# SAMD21.net
KiCad netlist of a schematic drawn in Altium Designer
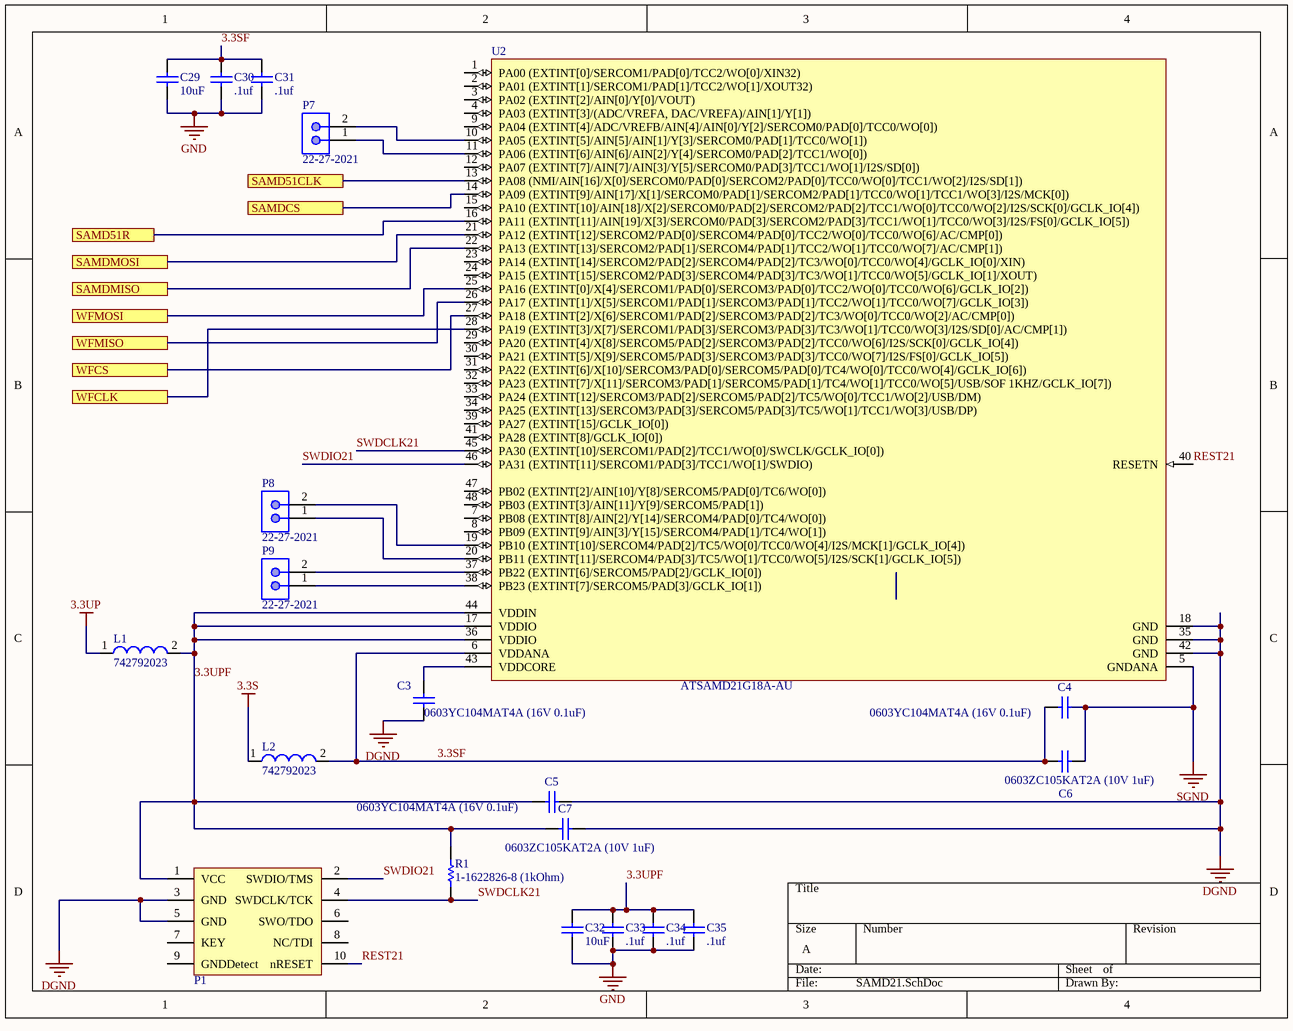
[diagram p0: SAMD21.SchDoc]

(export (version "E")
  (design (tool "Eeschema 10.0.6"))
  (components
    (comp (ref "C3")
      (value "0603YC104MAT4A (16V 0.1uF)")
      (footprint "CAPC1608X90X35LL15T15")
      (fields
        (field (name "PART NUMBER") "0603YC104MAT4A")
        (field (name "MANUFACTURER") "AVX Interconnect / Elco")
      )
      (libsource (lib "Altium Content Vault") (part "CAP"))
    )
    (comp (ref "C4")
      (value "0603YC104MAT4A (16V 0.1uF)")
      (footprint "CAPC1608X90X35LL15T15")
      (fields
        (field (name "PART NUMBER") "0603YC104MAT4A")
        (field (name "MANUFACTURER") "AVX Interconnect / Elco")
      )
      (libsource (lib "Altium Content Vault") (part "CAP"))
    )
    (comp (ref "C5")
      (value "0603YC104MAT4A (16V 0.1uF)")
      (footprint "CAPC1608X90X35LL15T15")
      (fields
        (field (name "PART NUMBER") "0603YC104MAT4A")
        (field (name "MANUFACTURER") "AVX Interconnect / Elco")
      )
      (libsource (lib "Altium Content Vault") (part "CAP"))
    )
    (comp (ref "C6")
      (value "0603ZC105KAT2A (10V 1uF)")
      (footprint "CAPC1608X90X35LL15T15")
      (fields
        (field (name "PART NUMBER") "0603ZC105KAT2A")
        (field (name "MANUFACTURER") "AVX Interconnect / Elco")
      )
      (libsource (lib "Altium Content Vault") (part "CAP"))
    )
    (comp (ref "C7")
      (value "0603ZC105KAT2A (10V 1uF)")
      (footprint "CAPC1608X90X35LL15T15")
      (fields
        (field (name "PART NUMBER") "0603ZC105KAT2A")
        (field (name "MANUFACTURER") "AVX Interconnect / Elco")
      )
      (libsource (lib "Altium Content Vault") (part "CAP"))
    )
    (comp (ref "C29")
      (value "10uF")
      (footprint "CAPC1608X90X35NL10T15")
      (fields (field (name "PART NUMBER") "GRM188R60J106ME47D") (field (name "MANUFACTURER") "Murata"))
      (libsource (lib "Altium Content Vault") (part "CAP"))
    )
    (comp (ref "C30")
      (value ".1uf")
      (footprint "CAPC2013X94X50NL20T25")
      (fields
        (field (name "PART NUMBER") "0805YC104KAT2A")
        (field (name "MANUFACTURER") "AVX Interconnect / Elco")
      )
      (libsource (lib "Altium Content Vault") (part "CAP"))
    )
    (comp (ref "C31")
      (value ".1uf")
      (footprint "CAPC2013X94X50NL20T25")
      (fields
        (field (name "PART NUMBER") "0805YC104KAT2A")
        (field (name "MANUFACTURER") "AVX Interconnect / Elco")
      )
      (libsource (lib "Altium Content Vault") (part "CAP"))
    )
    (comp (ref "C32")
      (value "10uF")
      (footprint "CAPC1608X90X35NL10T15")
      (fields (field (name "PART NUMBER") "GRM188R60J106ME47D") (field (name "MANUFACTURER") "Murata"))
      (libsource (lib "Altium Content Vault") (part "CAP"))
    )
    (comp (ref "C33")
      (value ".1uf")
      (footprint "CAPC2013X94X50NL20T25")
      (fields
        (field (name "PART NUMBER") "0805YC104KAT2A")
        (field (name "MANUFACTURER") "AVX Interconnect / Elco")
      )
      (libsource (lib "Altium Content Vault") (part "CAP"))
    )
    (comp (ref "C34")
      (value ".1uf")
      (footprint "CAPC2013X94X50NL20T25")
      (fields
        (field (name "PART NUMBER") "0805YC104KAT2A")
        (field (name "MANUFACTURER") "AVX Interconnect / Elco")
      )
      (libsource (lib "Altium Content Vault") (part "CAP"))
    )
    (comp (ref "C35")
      (value ".1uf")
      (footprint "CAPC2013X94X50NL20T25")
      (fields
        (field (name "PART NUMBER") "0805YC104KAT2A")
        (field (name "MANUFACTURER") "AVX Interconnect / Elco")
      )
      (libsource (lib "Altium Content Vault") (part "CAP"))
    )
    (comp (ref "L1")
      (value "742792023")
      (footprint "SMD-0805")
      (description "SMD EMI Suppression Ferrite Bead WE-CBF, Z = 120 Ohm")
      (libsource (lib "Altium Content Vault") (part "PAS-IND-INDUCTOR-2"))
    )
    (comp (ref "L2")
      (value "742792023")
      (footprint "SMD-0805")
      (description "SMD EMI Suppression Ferrite Bead WE-CBF, Z = 120 Ohm")
      (libsource (lib "Altium Content Vault") (part "PAS-IND-INDUCTOR-2"))
    )
    (comp (ref "P1")
      (value "3220-10-0100-00 Pin connector for Cotex Programmers")
      (description "3220-10-0100-00 Pin connector from DigiKey")
      (libsource (lib "3220-10-0100-00") (part "3220-10-0100-00"))
    )
    (comp (ref "P7")
      (value "22-27-2021")
      (footprint "MOLX-22-27-2021_V")
      (fields (field (name "MANUFACTURER") "Molex") (field (name "PARTNUMBER") "0022272021"))
      (libsource (lib "Altium Content Vault") (part "CN-1P-M-R2"))
    )
    (comp (ref "P8")
      (value "22-27-2021")
      (footprint "MOLX-22-27-2021_V")
      (fields (field (name "MANUFACTURER") "Molex") (field (name "PARTNUMBER") "0022272021"))
      (libsource (lib "Altium Content Vault") (part "CN-1P-M-R2"))
    )
    (comp (ref "P9")
      (value "22-27-2021")
      (footprint "MOLX-22-27-2021_V")
      (fields (field (name "MANUFACTURER") "Molex") (field (name "PARTNUMBER") "0022272021"))
      (libsource (lib "Altium Content Vault") (part "CN-1P-M-R2"))
    )
    (comp (ref "R1")
      (value "1-1622826-8 (1kOhm)")
      (footprint "RESC1005X40X25ML10T10")
      (fields
        (field (name "MANUFACTURER") "TE Connectivity / AMP")
        (field (name "PART NUMBER") "1-1622826-8")
      )
      (libsource (lib "Altium Content Vault") (part "RES"))
    )
    (comp (ref "U2")
      (value "ATSAMD21G18A-AU")
      (footprint "ATML-TQFP48_M")
      (fields (field (name "MANUFACTURER") "Atmel"))
      (libsource (lib "Altium Content Vault") (part "ATML-ATSAMD21G18_17_16_15A-TQFP48"))
    )
  )
  (nets
    (net (code "1") (name "/3.3SF") (class "Default")
      (node (ref "C29") (pin "2") (pinfunction "2_2") (pintype "passive"))
      (node (ref "C30") (pin "2") (pinfunction "2_2") (pintype "passive"))
      (node (ref "C31") (pin "2") (pinfunction "2_2") (pintype "passive"))
      (node (ref "C4") (pin "2") (pinfunction "2_2") (pintype "passive"))
      (node (ref "C6") (pin "1") (pinfunction "1_1") (pintype "passive"))
      (node (ref "L2") (pin "2") (pinfunction "2_2") (pintype "passive"))
      (node (ref "U2") (pin "6") (pinfunction "VDDANA_6") (pintype "power_in"))
    )
    (net (code "2") (name "/3.3UPF") (class "Default")
      (node (ref "C32") (pin "2") (pinfunction "2_2") (pintype "passive"))
      (node (ref "C33") (pin "2") (pinfunction "2_2") (pintype "passive"))
      (node (ref "C34") (pin "2") (pinfunction "2_2") (pintype "passive"))
      (node (ref "C35") (pin "2") (pinfunction "2_2") (pintype "passive"))
      (node (ref "C5") (pin "2") (pinfunction "2_2") (pintype "passive"))
      (node (ref "C7") (pin "1") (pinfunction "1_1") (pintype "passive"))
      (node (ref "L1") (pin "2") (pinfunction "2_2") (pintype "passive"))
      (node (ref "P1") (pin "1") (pinfunction "VCC_1") (pintype "passive"))
      (node (ref "R1") (pin "2") (pinfunction "2_2") (pintype "passive"))
      (node (ref "U2") (pin "17") (pinfunction "VDDIO_17") (pintype "power_in"))
      (node (ref "U2") (pin "36") (pinfunction "VDDIO_36") (pintype "power_in"))
      (node (ref "U2") (pin "44") (pinfunction "VDDIN_44") (pintype "power_in"))
    )
    (net (code "3") (name "/REST21") (class "Default")
      (node (ref "P1") (pin "10") (pinfunction "nRESET_10") (pintype "passive"))
      (node (ref "U2") (pin "40") (pinfunction "RESETN_40") (pintype "input"))
    )
    (net (code "4") (name "/SAMD51CLK") (class "Default")
      (node (ref "U2") (pin "13") (pinfunction "PA08_(NMI/AIN[16]/X[0]/SERCOM0/PAD[0]/SERCOM2/PAD[0]/TCC0/WO[0]/TCC1/WO[2]/I2S/SD[1])_13") (pintype "bidirectional"))
    )
    (net (code "5") (name "/SAMD51R") (class "Default")
      (node (ref "U2") (pin "16") (pinfunction "PA11_(EXTINT[11]/AIN[19]/X[3]/SERCOM0/PAD[3]/SERCOM2/PAD[3]/TCC1/WO[1]/TCC0/WO[3]/I2S/FS[0]/GCLK_IO[5])_16") (pintype "bidirectional"))
    )
    (net (code "6") (name "/SAMDCS") (class "Default")
      (node (ref "U2") (pin "14") (pinfunction "PA09_(EXTINT[9]/AIN[17]/X[1]/SERCOM0/PAD[1]/SERCOM2/PAD[1]/TCC0/WO[1]/TCC1/WO[3]/I2S/MCK[0])_14") (pintype "bidirectional"))
    )
    (net (code "7") (name "/SAMDMISO") (class "Default")
      (node (ref "U2") (pin "22") (pinfunction "PA13_(EXTINT[13]/SERCOM2/PAD[1]/SERCOM4/PAD[1]/TCC2/WO[1]/TCC0/WO[7]/AC/CMP[1])_22") (pintype "bidirectional"))
    )
    (net (code "8") (name "/SAMDMOSI") (class "Default")
      (node (ref "U2") (pin "21") (pinfunction "PA12_(EXTINT[12]/SERCOM2/PAD[0]/SERCOM4/PAD[0]/TCC2/WO[0]/TCC0/WO[6]/AC/CMP[0])_21") (pintype "bidirectional"))
    )
    (net (code "9") (name "/SWDCLK21") (class "Default")
      (node (ref "P1") (pin "4") (pinfunction "SWDCLK/TCK_4") (pintype "passive"))
      (node (ref "R1") (pin "1") (pinfunction "1_1") (pintype "passive"))
      (node (ref "U2") (pin "45") (pinfunction "PA30_(EXTINT[10]/SERCOM1/PAD[2]/TCC1/WO[0]/SWCLK/GCLK_IO[0])_45") (pintype "bidirectional"))
    )
    (net (code "10") (name "/SWDIO21") (class "Default")
      (node (ref "P1") (pin "2") (pinfunction "SWDIO/TMS_2") (pintype "passive"))
      (node (ref "U2") (pin "46") (pinfunction "PA31_(EXTINT[11]/SERCOM1/PAD[3]/TCC1/WO[1]/SWDIO)_46") (pintype "bidirectional"))
    )
    (net (code "11") (name "/WFCLK") (class "Default")
      (node (ref "U2") (pin "28") (pinfunction "PA19_(EXTINT[3]/X[7]/SERCOM1/PAD[3]/SERCOM3/PAD[3]/TC3/WO[1]/TCC0/WO[3]/I2S/SD[0]/AC/CMP[1])_28") (pintype "bidirectional"))
    )
    (net (code "12") (name "/WFCS") (class "Default")
      (node (ref "U2") (pin "27") (pinfunction "PA18_(EXTINT[2]/X[6]/SERCOM1/PAD[2]/SERCOM3/PAD[2]/TC3/WO[0]/TCC0/WO[2]/AC/CMP[0])_27") (pintype "bidirectional"))
    )
    (net (code "13") (name "/WFMISO") (class "Default")
      (node (ref "U2") (pin "26") (pinfunction "PA17_(EXTINT[1]/X[5]/SERCOM1/PAD[1]/SERCOM3/PAD[1]/TCC2/WO[1]/TCC0/WO[7]/GCLK_IO[3])_26") (pintype "bidirectional"))
    )
    (net (code "14") (name "/WFMOSI") (class "Default")
      (node (ref "U2") (pin "25") (pinfunction "PA16_(EXTINT[0]/X[4]/SERCOM1/PAD[0]/SERCOM3/PAD[0]/TCC2/WO[0]/TCC0/WO[6]/GCLK_IO[2])_25") (pintype "bidirectional"))
    )
    (net (code "15") (name "3.3S") (class "Default")
      (node (ref "L2") (pin "1") (pinfunction "1_1") (pintype "passive"))
    )
    (net (code "16") (name "3.3UP") (class "Default")
      (node (ref "L1") (pin "1") (pinfunction "1_1") (pintype "passive"))
    )
    (net (code "17") (name "DGND") (class "Default")
      (node (ref "C3") (pin "2") (pinfunction "2_2") (pintype "passive"))
      (node (ref "C5") (pin "1") (pinfunction "1_1") (pintype "passive"))
      (node (ref "C7") (pin "2") (pinfunction "2_2") (pintype "passive"))
      (node (ref "P1") (pin "3") (pinfunction "GND_3") (pintype "passive"))
      (node (ref "P1") (pin "5") (pinfunction "GND_5") (pintype "passive"))
      (node (ref "U2") (pin "18") (pinfunction "GND_18") (pintype "power_in"))
      (node (ref "U2") (pin "35") (pinfunction "GND_35") (pintype "power_in"))
      (node (ref "U2") (pin "42") (pinfunction "GND_42") (pintype "power_in"))
    )
    (net (code "18") (name "GND") (class "Default")
      (node (ref "C29") (pin "1") (pinfunction "1_1") (pintype "passive"))
      (node (ref "C30") (pin "1") (pinfunction "1_1") (pintype "passive"))
      (node (ref "C31") (pin "1") (pinfunction "1_1") (pintype "passive"))
      (node (ref "C32") (pin "1") (pinfunction "1_1") (pintype "passive"))
      (node (ref "C33") (pin "1") (pinfunction "1_1") (pintype "passive"))
      (node (ref "C34") (pin "1") (pinfunction "1_1") (pintype "passive"))
      (node (ref "C35") (pin "1") (pinfunction "1_1") (pintype "passive"))
    )
    (net (code "19") (name "Net-(U2-PA05_(EXTINT[5]{slash}AIN[5]{slash}AIN[1]{slash}Y[3]{slash}SERCOM0{slash}PAD[1]{slash}TCC0{slash}WO[1]))") (class "Default")
      (node (ref "P7") (pin "2") (pinfunction "2_2") (pintype "passive"))
      (node (ref "U2") (pin "10") (pinfunction "PA05_(EXTINT[5]/AIN[5]/AIN[1]/Y[3]/SERCOM0/PAD[1]/TCC0/WO[1])_10") (pintype "bidirectional"))
    )
    (net (code "20") (name "Net-(U2-PA06_(EXTINT[6]{slash}AIN[6]{slash}AIN[2]{slash}Y[4]{slash}SERCOM0{slash}PAD[2]{slash}TCC1{slash}WO[0]))") (class "Default")
      (node (ref "P7") (pin "1") (pinfunction "1_1") (pintype "passive"))
      (node (ref "U2") (pin "11") (pinfunction "PA06_(EXTINT[6]/AIN[6]/AIN[2]/Y[4]/SERCOM0/PAD[2]/TCC1/WO[0])_11") (pintype "bidirectional"))
    )
    (net (code "21") (name "Net-(U2-PB10_(EXTINT[10]{slash}SERCOM4{slash}PAD[2]{slash}TC5{slash}WO[0]{slash}TCC0{slash}WO[4]{slash}I2S{slash}MCK[1]{slash}GCLK_IO[4]))") (class "Default")
      (node (ref "P8") (pin "2") (pinfunction "2_2") (pintype "passive"))
      (node (ref "U2") (pin "19") (pinfunction "PB10_(EXTINT[10]/SERCOM4/PAD[2]/TC5/WO[0]/TCC0/WO[4]/I2S/MCK[1]/GCLK_IO[4])_19") (pintype "bidirectional"))
    )
    (net (code "22") (name "Net-(U2-PB11_(EXTINT[11]{slash}SERCOM4{slash}PAD[3]{slash}TC5{slash}WO[1]{slash}TCC0{slash}WO[5]{slash}I2S{slash}SCK[1]{slash}GCLK_IO[5]))") (class "Default")
      (node (ref "P8") (pin "1") (pinfunction "1_1") (pintype "passive"))
      (node (ref "U2") (pin "20") (pinfunction "PB11_(EXTINT[11]/SERCOM4/PAD[3]/TC5/WO[1]/TCC0/WO[5]/I2S/SCK[1]/GCLK_IO[5])_20") (pintype "bidirectional"))
    )
    (net (code "23") (name "Net-(U2-PB22_(EXTINT[6]{slash}SERCOM5{slash}PAD[2]{slash}GCLK_IO[0]))") (class "Default")
      (node (ref "P9") (pin "2") (pinfunction "2_2") (pintype "passive"))
      (node (ref "U2") (pin "37") (pinfunction "PB22_(EXTINT[6]/SERCOM5/PAD[2]/GCLK_IO[0])_37") (pintype "bidirectional"))
    )
    (net (code "24") (name "Net-(U2-PB23_(EXTINT[7]{slash}SERCOM5{slash}PAD[3]{slash}GCLK_IO[1]))") (class "Default")
      (node (ref "P9") (pin "1") (pinfunction "1_1") (pintype "passive"))
      (node (ref "U2") (pin "38") (pinfunction "PB23_(EXTINT[7]/SERCOM5/PAD[3]/GCLK_IO[1])_38") (pintype "bidirectional"))
    )
    (net (code "25") (name "Net-(U2-VDDCORE)") (class "Default")
      (node (ref "C3") (pin "1") (pinfunction "1_1") (pintype "passive"))
      (node (ref "U2") (pin "43") (pinfunction "VDDCORE_43") (pintype "power_in"))
    )
    (net (code "26") (name "SGND") (class "Default")
      (node (ref "C4") (pin "1") (pinfunction "1_1") (pintype "passive"))
      (node (ref "C6") (pin "2") (pinfunction "2_2") (pintype "passive"))
      (node (ref "U2") (pin "5") (pinfunction "GNDANA_5") (pintype "power_in"))
    )
    (net (code "27") (name "unconnected-(P1-GNDDetect-Pad9)") (class "Default")
      (node (ref "P1") (pin "9") (pinfunction "GNDDetect_9") (pintype "passive"))
    )
    (net (code "28") (name "unconnected-(P1-KEY-Pad7)") (class "Default")
      (node (ref "P1") (pin "7") (pinfunction "KEY_7") (pintype "passive"))
    )
    (net (code "29") (name "unconnected-(P1-NC{slash}TDI-Pad8)") (class "Default")
      (node (ref "P1") (pin "8") (pinfunction "NC/TDI_8") (pintype "passive"))
    )
    (net (code "30") (name "unconnected-(P1-SWO{slash}TDO-Pad6)") (class "Default")
      (node (ref "P1") (pin "6") (pinfunction "SWO/TDO_6") (pintype "passive"))
    )
    (net (code "31") (name "unconnected-(U2-PA00_(EXTINT[0]{slash}SERCOM1{slash}PAD[0]{slash}TCC2{slash}WO[0]{slash}XIN32)-Pad1)") (class "Default")
      (node (ref "U2") (pin "1") (pinfunction "PA00_(EXTINT[0]/SERCOM1/PAD[0]/TCC2/WO[0]/XIN32)_1") (pintype "bidirectional"))
    )
    (net (code "32") (name "unconnected-(U2-PA01_(EXTINT[1]{slash}SERCOM1{slash}PAD[1]{slash}TCC2{slash}WO[1]{slash}XOUT32)-Pad2)") (class "Default")
      (node (ref "U2") (pin "2") (pinfunction "PA01_(EXTINT[1]/SERCOM1/PAD[1]/TCC2/WO[1]/XOUT32)_2") (pintype "bidirectional"))
    )
    (net (code "33") (name "unconnected-(U2-PA02_(EXTINT[2]{slash}AIN[0]{slash}Y[0]{slash}VOUT)-Pad3)") (class "Default")
      (node (ref "U2") (pin "3") (pinfunction "PA02_(EXTINT[2]/AIN[0]/Y[0]/VOUT)_3") (pintype "bidirectional"))
    )
    (net (code "34") (name "unconnected-(U2-PA03_(EXTINT[3]{slash}(ADC{slash}VREFA,_DAC{slash}VREFA){slash}AIN[1]{slash}Y[1])-Pad4)") (class "Default")
      (node (ref "U2") (pin "4") (pinfunction "PA03_(EXTINT[3]/(ADC/VREFA,_DAC/VREFA)/AIN[1]/Y[1])_4") (pintype "bidirectional"))
    )
    (net (code "35") (name "unconnected-(U2-PA04_(EXTINT[4]{slash}ADC{slash}VREFB{slash}AIN[4]{slash}AIN[0]{slash}Y[2]{slash}SERCOM0{slash}PAD[0]{slash}TCC0{slash}WO[0])-Pad9)") (class "Default")
      (node (ref "U2") (pin "9") (pinfunction "PA04_(EXTINT[4]/ADC/VREFB/AIN[4]/AIN[0]/Y[2]/SERCOM0/PAD[0]/TCC0/WO[0])_9") (pintype "bidirectional"))
    )
    (net (code "36") (name "unconnected-(U2-PA07_(EXTINT[7]{slash}AIN[7]{slash}AIN[3]{slash}Y[5]{slash}SERCOM0{slash}PAD[3]{slash}TCC1{slash}WO[1]{slash}I2S{slash}SD[0])-Pad12)") (class "Default")
      (node (ref "U2") (pin "12") (pinfunction "PA07_(EXTINT[7]/AIN[7]/AIN[3]/Y[5]/SERCOM0/PAD[3]/TCC1/WO[1]/I2S/SD[0])_12") (pintype "bidirectional"))
    )
    (net (code "37") (name "unconnected-(U2-PA10_(EXTINT[10]{slash}AIN[18]{slash}X[2]{slash}SERCOM0{slash}PAD[2]{slash}SERCOM2{slash}PAD[2]{slash}TCC1{slash}WO[0]{slash}TCC0{slash}WO[2]{slash}I2S{slash}SCK[0]{slash}GCLK_IO[4])-Pad15)") (class "Default")
      (node (ref "U2") (pin "15") (pinfunction "PA10_(EXTINT[10]/AIN[18]/X[2]/SERCOM0/PAD[2]/SERCOM2/PAD[2]/TCC1/WO[0]/TCC0/WO[2]/I2S/SCK[0]/GCLK_IO[4])_15") (pintype "bidirectional"))
    )
    (net (code "38") (name "unconnected-(U2-PA14_(EXTINT[14]{slash}SERCOM2{slash}PAD[2]{slash}SERCOM4{slash}PAD[2]{slash}TC3{slash}WO[0]{slash}TCC0{slash}WO[4]{slash}GCLK_IO[0]{slash}XIN)-Pad23)") (class "Default")
      (node (ref "U2") (pin "23") (pinfunction "PA14_(EXTINT[14]/SERCOM2/PAD[2]/SERCOM4/PAD[2]/TC3/WO[0]/TCC0/WO[4]/GCLK_IO[0]/XIN)_23") (pintype "bidirectional"))
    )
    (net (code "39") (name "unconnected-(U2-PA15_(EXTINT[15]{slash}SERCOM2{slash}PAD[3]{slash}SERCOM4{slash}PAD[3]{slash}TC3{slash}WO[1]{slash}TCC0{slash}WO[5]{slash}GCLK_IO[1]{slash}XOUT)-Pad24)") (class "Default")
      (node (ref "U2") (pin "24") (pinfunction "PA15_(EXTINT[15]/SERCOM2/PAD[3]/SERCOM4/PAD[3]/TC3/WO[1]/TCC0/WO[5]/GCLK_IO[1]/XOUT)_24") (pintype "bidirectional"))
    )
    (net (code "40") (name "unconnected-(U2-PA20_(EXTINT[4]{slash}X[8]{slash}SERCOM5{slash}PAD[2]{slash}SERCOM3{slash}PAD[2]{slash}TCC0{slash}WO[6]{slash}I2S{slash}SCK[0]{slash}GCLK_IO[4])-Pad29)") (class "Default")
      (node (ref "U2") (pin "29") (pinfunction "PA20_(EXTINT[4]/X[8]/SERCOM5/PAD[2]/SERCOM3/PAD[2]/TCC0/WO[6]/I2S/SCK[0]/GCLK_IO[4])_29") (pintype "bidirectional"))
    )
    (net (code "41") (name "unconnected-(U2-PA21_(EXTINT[5]{slash}X[9]{slash}SERCOM5{slash}PAD[3]{slash}SERCOM3{slash}PAD[3]{slash}TCC0{slash}WO[7]{slash}I2S{slash}FS[0]{slash}GCLK_IO[5])-Pad30)") (class "Default")
      (node (ref "U2") (pin "30") (pinfunction "PA21_(EXTINT[5]/X[9]/SERCOM5/PAD[3]/SERCOM3/PAD[3]/TCC0/WO[7]/I2S/FS[0]/GCLK_IO[5])_30") (pintype "bidirectional"))
    )
    (net (code "42") (name "unconnected-(U2-PA22_(EXTINT[6]{slash}X[10]{slash}SERCOM3{slash}PAD[0]{slash}SERCOM5{slash}PAD[0]{slash}TC4{slash}WO[0]{slash}TCC0{slash}WO[4]{slash}GCLK_IO[6])-Pad31)") (class "Default")
      (node (ref "U2") (pin "31") (pinfunction "PA22_(EXTINT[6]/X[10]/SERCOM3/PAD[0]/SERCOM5/PAD[0]/TC4/WO[0]/TCC0/WO[4]/GCLK_IO[6])_31") (pintype "bidirectional"))
    )
    (net (code "43") (name "unconnected-(U2-PA23_(EXTINT[7]{slash}X[11]{slash}SERCOM3{slash}PAD[1]{slash}SERCOM5{slash}PAD[1]{slash}TC4{slash}WO[1]{slash}TCC0{slash}WO[5]{slash}USB{slash}SOF_1KHZ{slash}GCLK_IO[7])-Pad32)") (class "Default")
      (node (ref "U2") (pin "32") (pinfunction "PA23_(EXTINT[7]/X[11]/SERCOM3/PAD[1]/SERCOM5/PAD[1]/TC4/WO[1]/TCC0/WO[5]/USB/SOF_1KHZ/GCLK_IO[7])_32") (pintype "bidirectional"))
    )
    (net (code "44") (name "unconnected-(U2-PA24_(EXTINT[12]{slash}SERCOM3{slash}PAD[2]{slash}SERCOM5{slash}PAD[2]{slash}TC5{slash}WO[0]{slash}TCC1{slash}WO[2]{slash}USB{slash}DM)-Pad33)") (class "Default")
      (node (ref "U2") (pin "33") (pinfunction "PA24_(EXTINT[12]/SERCOM3/PAD[2]/SERCOM5/PAD[2]/TC5/WO[0]/TCC1/WO[2]/USB/DM)_33") (pintype "bidirectional"))
    )
    (net (code "45") (name "unconnected-(U2-PA25_(EXTINT[13]{slash}SERCOM3{slash}PAD[3]{slash}SERCOM5{slash}PAD[3]{slash}TC5{slash}WO[1]{slash}TCC1{slash}WO[3]{slash}USB{slash}DP)-Pad34)") (class "Default")
      (node (ref "U2") (pin "34") (pinfunction "PA25_(EXTINT[13]/SERCOM3/PAD[3]/SERCOM5/PAD[3]/TC5/WO[1]/TCC1/WO[3]/USB/DP)_34") (pintype "bidirectional"))
    )
    (net (code "46") (name "unconnected-(U2-PA27_(EXTINT[15]{slash}GCLK_IO[0])-Pad39)") (class "Default")
      (node (ref "U2") (pin "39") (pinfunction "PA27_(EXTINT[15]/GCLK_IO[0])_39") (pintype "bidirectional"))
    )
    (net (code "47") (name "unconnected-(U2-PA28_(EXTINT[8]{slash}GCLK_IO[0])-Pad41)") (class "Default")
      (node (ref "U2") (pin "41") (pinfunction "PA28_(EXTINT[8]/GCLK_IO[0])_41") (pintype "bidirectional"))
    )
    (net (code "48") (name "unconnected-(U2-PB02_(EXTINT[2]{slash}AIN[10]{slash}Y[8]{slash}SERCOM5{slash}PAD[0]{slash}TC6{slash}WO[0])-Pad47)") (class "Default")
      (node (ref "U2") (pin "47") (pinfunction "PB02_(EXTINT[2]/AIN[10]/Y[8]/SERCOM5/PAD[0]/TC6/WO[0])_47") (pintype "bidirectional"))
    )
    (net (code "49") (name "unconnected-(U2-PB03_(EXTINT[3]{slash}AIN[11]{slash}Y[9]{slash}SERCOM5{slash}PAD[1])-Pad48)") (class "Default")
      (node (ref "U2") (pin "48") (pinfunction "PB03_(EXTINT[3]/AIN[11]/Y[9]/SERCOM5/PAD[1])_48") (pintype "bidirectional"))
    )
    (net (code "50") (name "unconnected-(U2-PB08_(EXTINT[8]{slash}AIN[2]{slash}Y[14]{slash}SERCOM4{slash}PAD[0]{slash}TC4{slash}WO[0])-Pad7)") (class "Default")
      (node (ref "U2") (pin "7") (pinfunction "PB08_(EXTINT[8]/AIN[2]/Y[14]/SERCOM4/PAD[0]/TC4/WO[0])_7") (pintype "bidirectional"))
    )
    (net (code "51") (name "unconnected-(U2-PB09_(EXTINT[9]{slash}AIN[3]{slash}Y[15]{slash}SERCOM4{slash}PAD[1]{slash}TC4{slash}WO[1])-Pad8)") (class "Default")
      (node (ref "U2") (pin "8") (pinfunction "PB09_(EXTINT[9]/AIN[3]/Y[15]/SERCOM4/PAD[1]/TC4/WO[1])_8") (pintype "bidirectional"))
    )
  )
)
